# CAN_MicroSDD_IO_Expandor.net
KiCad netlist of a schematic drawn in Altium Designer
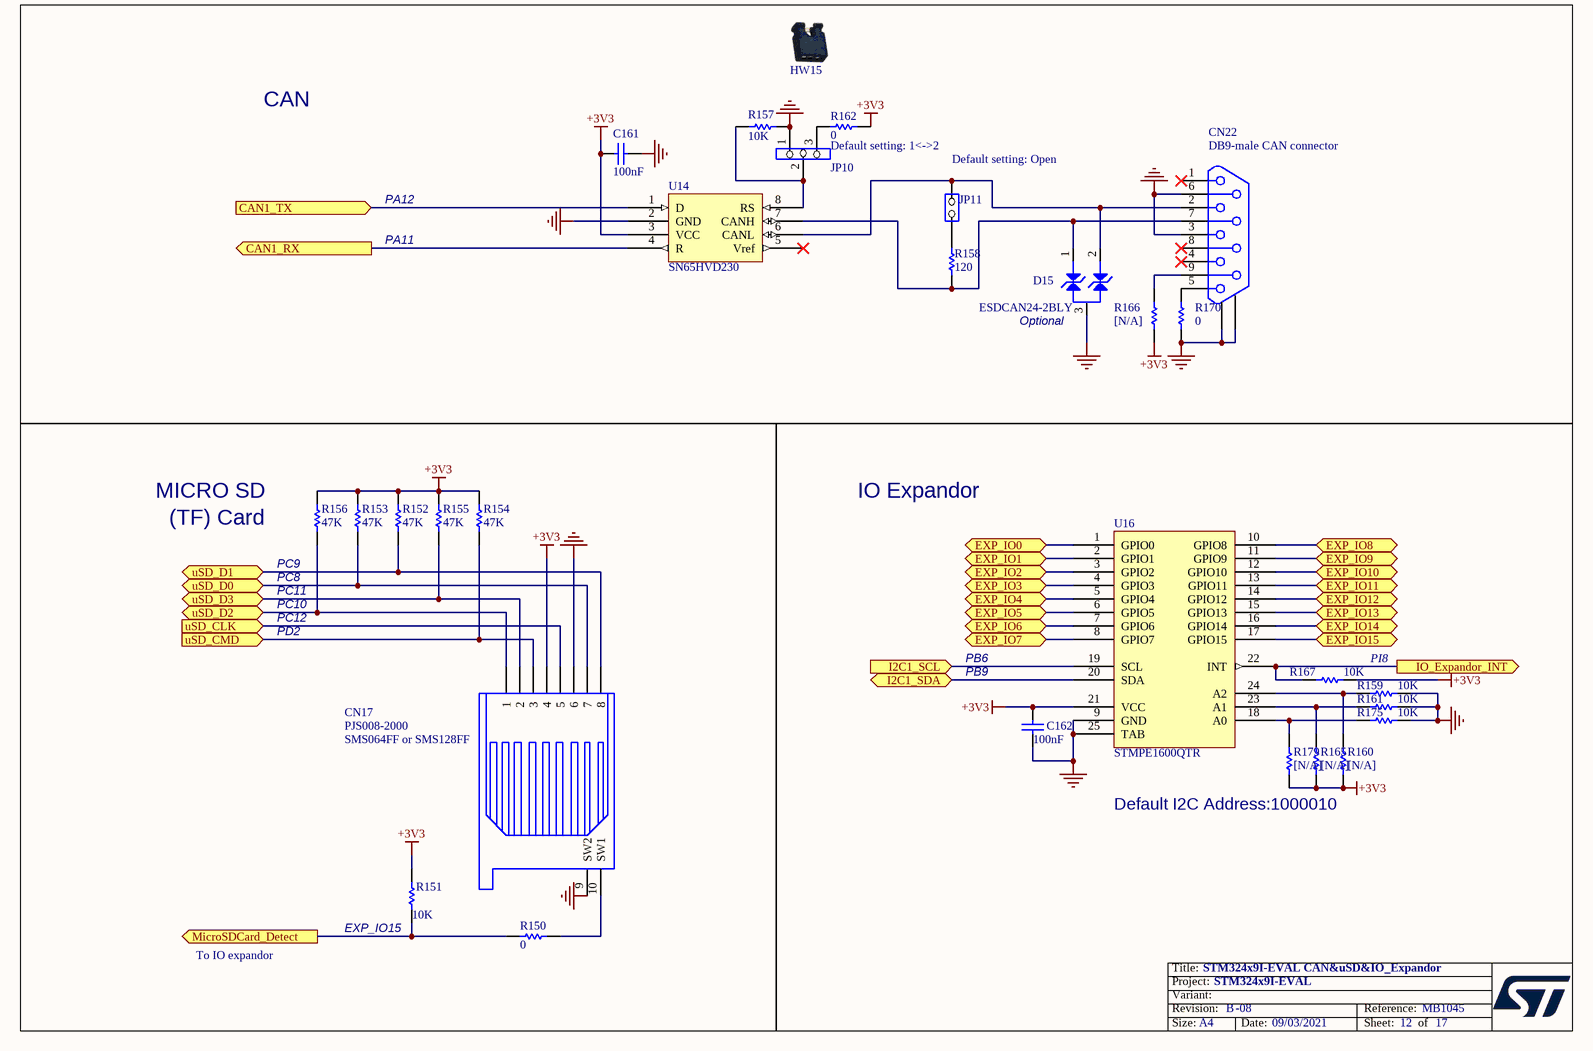
[diagram p0: CAN&MicroSDD&IO_Expandor.SchDoc]

(export (version "E")
  (design (tool "Eeschema 10.0.6"))
  (components
    (comp (ref "C161")
      (value "100nF")
      (footprint "0603C")
      (description "Capacitor")
      (fields (field (name "PUBLISHER") "Altium Limited"))
      (libsource (lib "Miscellaneous Devices") (part "Cap"))
    )
    (comp (ref "C162")
      (value "100nF")
      (footprint "0603C")
      (description "Capacitor")
      (fields (field (name "PUBLISHER") "Altium Limited"))
      (libsource (lib "Miscellaneous Devices") (part "Cap"))
    )
    (comp (ref "CN17")
      (value "PJS008-2000")
      (footprint "MSD_PJS008_")
      (libsource (lib "MB525") (part "SMS016AFA5E"))
    )
    (comp (ref "CN22")
      (value "DB9-male CAN connector")
      (footprint "DB9/M")
      (libsource (lib "mb1045") (part "DB9-CAN"))
    )
    (comp (ref "D15")
      (value "ESDCAN24-2BLY")
      (footprint "SOT23-213")
      (libsource (lib "mb1045") (part "ESDCAN24-2BLY"))
    )
    (comp (ref "HW15") (value "JUMPER_OPEN") (libsource (lib "mb1045") (part "JUMPER_OPEN")))
    (comp (ref "JP10") (value "~") (footprint "SIP3") (libsource (lib "STR910_SCHLIB") (part "Jumper3")))
    (comp (ref "JP11") (value "~") (footprint "SIP2") (libsource (lib "*") (part "JP2")))
    (comp (ref "R150")
      (value "0")
      (footprint "0603R")
      (description "Resistor")
      (fields (field (name "PUBLISHER") "Altium Limited"))
      (libsource (lib "Miscellaneous Devices") (part "Res1"))
    )
    (comp (ref "R151")
      (value "10K")
      (footprint "0603R")
      (description "Resistor")
      (fields (field (name "PUBLISHER") "Altium Limited"))
      (libsource (lib "Miscellaneous Devices") (part "Res1"))
    )
    (comp (ref "R152")
      (value "47K")
      (footprint "0603R")
      (description "Resistor")
      (fields (field (name "PUBLISHER") "Altium Limited"))
      (libsource (lib "Miscellaneous Devices") (part "res1"))
    )
    (comp (ref "R153")
      (value "47K")
      (footprint "0603R")
      (description "Resistor")
      (fields (field (name "PUBLISHER") "Altium Limited"))
      (libsource (lib "Miscellaneous Devices") (part "res1"))
    )
    (comp (ref "R154")
      (value "47K")
      (footprint "0603R")
      (description "Resistor")
      (fields (field (name "PUBLISHER") "Altium Limited"))
      (libsource (lib "Miscellaneous Devices") (part "res1"))
    )
    (comp (ref "R155")
      (value "47K")
      (footprint "0603R")
      (description "Resistor")
      (fields (field (name "PUBLISHER") "Altium Limited"))
      (libsource (lib "Miscellaneous Devices") (part "res1"))
    )
    (comp (ref "R156")
      (value "47K")
      (footprint "0603R")
      (description "Resistor")
      (fields (field (name "PUBLISHER") "Altium Limited"))
      (libsource (lib "Miscellaneous Devices") (part "res1"))
    )
    (comp (ref "R157")
      (value "10K")
      (footprint "0603R")
      (description "Resistor")
      (fields (field (name "PUBLISHER") "Altium Limited"))
      (libsource (lib "Miscellaneous Devices") (part "Res1"))
    )
    (comp (ref "R158")
      (value "120")
      (footprint "0603R")
      (description "Resistor")
      (fields (field (name "PUBLISHER") "Altium Limited"))
      (libsource (lib "Miscellaneous Devices") (part "res1"))
    )
    (comp (ref "R159")
      (value "10K")
      (footprint "0603R")
      (description "Resistor")
      (fields (field (name "PUBLISHER") "Altium Limited"))
      (libsource (lib "Miscellaneous Devices") (part "res1"))
    )
    (comp (ref "R160")
      (value "[N/A]")
      (footprint "0603R")
      (description "Resistor")
      (fields (field (name "PUBLISHER") "Altium Limited"))
      (libsource (lib "Miscellaneous Devices") (part "Res1"))
    )
    (comp (ref "R161")
      (value "10K")
      (footprint "0603R")
      (description "Resistor")
      (fields (field (name "PUBLISHER") "Altium Limited"))
      (libsource (lib "Miscellaneous Devices") (part "res1"))
    )
    (comp (ref "R162")
      (value "0")
      (footprint "0603R")
      (description "Resistor")
      (fields (field (name "PUBLISHER") "Altium Limited"))
      (libsource (lib "Miscellaneous Devices") (part "res1"))
    )
    (comp (ref "R165")
      (value "[N/A]")
      (footprint "0603R")
      (description "Resistor")
      (fields (field (name "PUBLISHER") "Altium Limited"))
      (libsource (lib "Miscellaneous Devices") (part "Res1"))
    )
    (comp (ref "R166")
      (value "[N/A]")
      (footprint "0603R")
      (description "Resistor")
      (fields (field (name "PUBLISHER") "Altium Limited"))
      (libsource (lib "Miscellaneous Devices") (part "res1"))
    )
    (comp (ref "R167")
      (value "10K")
      (footprint "0603R")
      (description "Resistor")
      (fields (field (name "PUBLISHER") "Altium Limited"))
      (libsource (lib "Miscellaneous Devices") (part "Res1"))
    )
    (comp (ref "R170")
      (value "0")
      (footprint "0603R")
      (description "Resistor")
      (fields (field (name "PUBLISHER") "Altium Limited"))
      (libsource (lib "Miscellaneous Devices") (part "res1"))
    )
    (comp (ref "R175")
      (value "10K")
      (footprint "0603R")
      (description "Resistor")
      (fields (field (name "PUBLISHER") "Altium Limited"))
      (libsource (lib "Miscellaneous Devices") (part "res1"))
    )
    (comp (ref "R179")
      (value "[N/A]")
      (footprint "0603R")
      (description "Resistor")
      (fields (field (name "PUBLISHER") "Altium Limited"))
      (libsource (lib "Miscellaneous Devices") (part "Res1"))
    )
    (comp (ref "U14")
      (value "SN65HVD230")
      (footprint "SOIC8_1R27_4R9X6")
      (libsource (lib "STR910_SCHLIB") (part "SN65HVD230D"))
    )
    (comp (ref "U16")
      (value "STMPE1600QTR")
      (footprint "QFN24_0R5_4X4")
      (libsource (lib "mb1045") (part "STMPE1600"))
    )
  )
  (nets
    (net (code "1") (name "+3V3") (class "Default")
      (node (ref "C161") (pin "1") (pinfunction "1_1") (pintype "passive"))
      (node (ref "C162") (pin "1") (pinfunction "1_1") (pintype "passive"))
      (node (ref "CN17") (pin "4") (pinfunction "4_4") (pintype "passive"))
      (node (ref "R151") (pin "2") (pinfunction "2_2") (pintype "passive"))
      (node (ref "R152") (pin "1") (pinfunction "1_1") (pintype "passive"))
      (node (ref "R153") (pin "1") (pinfunction "1_1") (pintype "passive"))
      (node (ref "R154") (pin "1") (pinfunction "1_1") (pintype "passive"))
      (node (ref "R155") (pin "1") (pinfunction "1_1") (pintype "passive"))
      (node (ref "R156") (pin "1") (pinfunction "1_1") (pintype "passive"))
      (node (ref "R160") (pin "1") (pinfunction "1_1") (pintype "passive"))
      (node (ref "R162") (pin "2") (pinfunction "2_2") (pintype "passive"))
      (node (ref "R165") (pin "1") (pinfunction "1_1") (pintype "passive"))
      (node (ref "R166") (pin "1") (pinfunction "1_1") (pintype "passive"))
      (node (ref "R167") (pin "1") (pinfunction "1_1") (pintype "passive"))
      (node (ref "R179") (pin "1") (pinfunction "1_1") (pintype "passive"))
      (node (ref "U14") (pin "3") (pinfunction "VCC_3") (pintype "power_in"))
      (node (ref "U16") (pin "21") (pinfunction "VCC_21") (pintype "passive"))
    )
    (net (code "2") (name "/CAN1_RX") (class "Default")
      (node (ref "U14") (pin "4") (pinfunction "R_4") (pintype "output"))
    )
    (net (code "3") (name "/CAN1_TX") (class "Default")
      (node (ref "U14") (pin "1") (pinfunction "D_1") (pintype "input"))
    )
    (net (code "4") (name "/EXP_IO0") (class "Default")
      (node (ref "U16") (pin "1") (pinfunction "GPIO0_1") (pintype "passive"))
    )
    (net (code "5") (name "/EXP_IO1") (class "Default")
      (node (ref "U16") (pin "2") (pinfunction "GPIO1_2") (pintype "passive"))
    )
    (net (code "6") (name "/EXP_IO2") (class "Default")
      (node (ref "U16") (pin "3") (pinfunction "GPIO2_3") (pintype "passive"))
    )
    (net (code "7") (name "/EXP_IO3") (class "Default")
      (node (ref "U16") (pin "4") (pinfunction "GPIO3_4") (pintype "passive"))
    )
    (net (code "8") (name "/EXP_IO4") (class "Default")
      (node (ref "U16") (pin "5") (pinfunction "GPIO4_5") (pintype "passive"))
    )
    (net (code "9") (name "/EXP_IO5") (class "Default")
      (node (ref "U16") (pin "6") (pinfunction "GPIO5_6") (pintype "passive"))
    )
    (net (code "10") (name "/EXP_IO6") (class "Default")
      (node (ref "U16") (pin "7") (pinfunction "GPIO6_7") (pintype "passive"))
    )
    (net (code "11") (name "/EXP_IO7") (class "Default")
      (node (ref "U16") (pin "8") (pinfunction "GPIO7_8") (pintype "passive"))
    )
    (net (code "12") (name "/EXP_IO8") (class "Default")
      (node (ref "U16") (pin "10") (pinfunction "GPIO8_10") (pintype "passive"))
    )
    (net (code "13") (name "/EXP_IO9") (class "Default")
      (node (ref "U16") (pin "11") (pinfunction "GPIO9_11") (pintype "passive"))
    )
    (net (code "14") (name "/EXP_IO10") (class "Default")
      (node (ref "U16") (pin "12") (pinfunction "GPIO10_12") (pintype "passive"))
    )
    (net (code "15") (name "/EXP_IO11") (class "Default")
      (node (ref "U16") (pin "13") (pinfunction "GPIO11_13") (pintype "passive"))
    )
    (net (code "16") (name "/EXP_IO12") (class "Default")
      (node (ref "U16") (pin "14") (pinfunction "GPIO12_14") (pintype "passive"))
    )
    (net (code "17") (name "/EXP_IO13") (class "Default")
      (node (ref "U16") (pin "15") (pinfunction "GPIO13_15") (pintype "passive"))
    )
    (net (code "18") (name "/EXP_IO14") (class "Default")
      (node (ref "U16") (pin "16") (pinfunction "GPIO14_16") (pintype "passive"))
    )
    (net (code "19") (name "/EXP_IO15") (class "Default")
      (node (ref "U16") (pin "17") (pinfunction "GPIO15_17") (pintype "passive"))
    )
    (net (code "20") (name "/I2C1_SCL") (class "Default")
      (node (ref "U16") (pin "19") (pinfunction "SCL_19") (pintype "passive"))
    )
    (net (code "21") (name "/I2C1_SDA") (class "Default")
      (node (ref "U16") (pin "20") (pinfunction "SDA_20") (pintype "passive"))
    )
    (net (code "22") (name "/IO_Expandor_INT") (class "Default")
      (node (ref "R167") (pin "2") (pinfunction "2_2") (pintype "passive"))
      (node (ref "U16") (pin "22") (pinfunction "INT_22") (pintype "output"))
    )
    (net (code "23") (name "/MicroSDCard_Detect") (class "Default")
      (node (ref "R150") (pin "1") (pinfunction "1_1") (pintype "passive"))
      (node (ref "R151") (pin "1") (pinfunction "1_1") (pintype "passive"))
    )
    (net (code "24") (name "/uSD_CLK") (class "Default")
      (node (ref "CN17") (pin "5") (pinfunction "5_5") (pintype "passive"))
    )
    (net (code "25") (name "/uSD_CMD") (class "Default")
      (node (ref "CN17") (pin "3") (pinfunction "3_3") (pintype "passive"))
      (node (ref "R154") (pin "2") (pinfunction "2_2") (pintype "passive"))
    )
    (net (code "26") (name "/uSD_D0") (class "Default")
      (node (ref "CN17") (pin "7") (pinfunction "7_7") (pintype "passive"))
      (node (ref "R153") (pin "2") (pinfunction "2_2") (pintype "passive"))
    )
    (net (code "27") (name "/uSD_D1") (class "Default")
      (node (ref "CN17") (pin "8") (pinfunction "8_8") (pintype "passive"))
      (node (ref "R152") (pin "2") (pinfunction "2_2") (pintype "passive"))
    )
    (net (code "28") (name "/uSD_D2") (class "Default")
      (node (ref "CN17") (pin "1") (pinfunction "1_1") (pintype "passive"))
      (node (ref "R156") (pin "2") (pinfunction "2_2") (pintype "passive"))
    )
    (net (code "29") (name "/uSD_D3") (class "Default")
      (node (ref "CN17") (pin "2") (pinfunction "2_2") (pintype "passive"))
      (node (ref "R155") (pin "2") (pinfunction "2_2") (pintype "passive"))
    )
    (net (code "30") (name "GND") (class "Default")
      (node (ref "C161") (pin "2") (pinfunction "2_2") (pintype "passive"))
      (node (ref "C162") (pin "2") (pinfunction "2_2") (pintype "passive"))
      (node (ref "CN17") (pin "6") (pinfunction "6_6") (pintype "passive"))
      (node (ref "CN17") (pin "9") (pinfunction "SW2_9") (pintype "passive"))
      (node (ref "CN22") (pin "10") (pinfunction "10_10") (pintype "passive"))
      (node (ref "CN22") (pin "11") (pinfunction "11_11") (pintype "passive"))
      (node (ref "CN22") (pin "3") (pinfunction "3_3") (pintype "passive"))
      (node (ref "CN22") (pin "6") (pinfunction "6_6") (pintype "passive"))
      (node (ref "D15") (pin "3") (pinfunction "3_3") (pintype "passive"))
      (node (ref "JP10") (pin "1") (pintype "passive"))
      (node (ref "R157") (pin "2") (pinfunction "2_2") (pintype "passive"))
      (node (ref "R159") (pin "1") (pinfunction "1_1") (pintype "passive"))
      (node (ref "R161") (pin "1") (pinfunction "1_1") (pintype "passive"))
      (node (ref "R170") (pin "1") (pinfunction "1_1") (pintype "passive"))
      (node (ref "R175") (pin "1") (pinfunction "1_1") (pintype "passive"))
      (node (ref "U14") (pin "2") (pinfunction "GND_2") (pintype "power_in"))
      (node (ref "U16") (pin "25") (pinfunction "TAB_25") (pintype "passive"))
      (node (ref "U16") (pin "9") (pinfunction "GND_9") (pintype "passive"))
    )
    (net (code "31") (name "Net-(CN17-SW1)") (class "Default")
      (node (ref "CN17") (pin "10") (pinfunction "SW1_10") (pintype "passive"))
      (node (ref "R150") (pin "2") (pinfunction "2_2") (pintype "passive"))
    )
    (net (code "32") (name "Net-(CN22-Pad5)") (class "Default")
      (node (ref "CN22") (pin "5") (pinfunction "5_5") (pintype "passive"))
      (node (ref "R170") (pin "2") (pinfunction "2_2") (pintype "passive"))
    )
    (net (code "33") (name "Net-(CN22-Pad9)") (class "Default")
      (node (ref "CN22") (pin "9") (pinfunction "9_9") (pintype "passive"))
      (node (ref "R166") (pin "2") (pinfunction "2_2") (pintype "passive"))
    )
    (net (code "34") (name "Net-(JP10-Pad3)") (class "Default")
      (node (ref "JP10") (pin "3") (pintype "passive"))
      (node (ref "R162") (pin "1") (pinfunction "1_1") (pintype "passive"))
    )
    (net (code "35") (name "Net-(JP11-COMMON)") (class "Default")
      (node (ref "JP11") (pin "1") (pinfunction "COMMON_1") (pintype "passive"))
      (node (ref "R158") (pin "2") (pinfunction "2_2") (pintype "passive"))
    )
    (net (code "36") (name "Net-(JP11-NO)") (class "Default")
      (node (ref "CN22") (pin "2") (pinfunction "2_2") (pintype "passive"))
      (node (ref "D15") (pin "2") (pinfunction "2_2") (pintype "passive"))
      (node (ref "JP11") (pin "2") (pinfunction "NO_2") (pintype "passive"))
      (node (ref "U14") (pin "6") (pinfunction "CANL_6") (pintype "bidirectional"))
    )
    (net (code "37") (name "Net-(U14-CANH)") (class "Default")
      (node (ref "CN22") (pin "7") (pinfunction "7_7") (pintype "passive"))
      (node (ref "D15") (pin "1") (pinfunction "1_1") (pintype "passive"))
      (node (ref "R158") (pin "1") (pinfunction "1_1") (pintype "passive"))
      (node (ref "U14") (pin "7") (pinfunction "CANH_7") (pintype "bidirectional"))
    )
    (net (code "38") (name "Net-(U14-RS)") (class "Default")
      (node (ref "JP10") (pin "2") (pintype "passive"))
      (node (ref "R157") (pin "1") (pinfunction "1_1") (pintype "passive"))
      (node (ref "U14") (pin "8") (pinfunction "RS_8") (pintype "input"))
    )
    (net (code "39") (name "Net-(U16-A0)") (class "Default")
      (node (ref "R175") (pin "2") (pinfunction "2_2") (pintype "passive"))
      (node (ref "R179") (pin "2") (pinfunction "2_2") (pintype "passive"))
      (node (ref "U16") (pin "18") (pinfunction "A0_18") (pintype "passive"))
    )
    (net (code "40") (name "Net-(U16-A1)") (class "Default")
      (node (ref "R161") (pin "2") (pinfunction "2_2") (pintype "passive"))
      (node (ref "R165") (pin "2") (pinfunction "2_2") (pintype "passive"))
      (node (ref "U16") (pin "23") (pinfunction "A1_23") (pintype "passive"))
    )
    (net (code "41") (name "Net-(U16-A2)") (class "Default")
      (node (ref "R159") (pin "2") (pinfunction "2_2") (pintype "passive"))
      (node (ref "R160") (pin "2") (pinfunction "2_2") (pintype "passive"))
      (node (ref "U16") (pin "24") (pinfunction "A2_24") (pintype "passive"))
    )
    (net (code "42") (name "unconnected-(CN22-Pad1)") (class "Default")
      (node (ref "CN22") (pin "1") (pinfunction "1_1") (pintype "passive+no_connect"))
    )
    (net (code "43") (name "unconnected-(CN22-Pad4)") (class "Default")
      (node (ref "CN22") (pin "4") (pinfunction "4_4") (pintype "passive+no_connect"))
    )
    (net (code "44") (name "unconnected-(CN22-Pad8)") (class "Default")
      (node (ref "CN22") (pin "8") (pinfunction "8_8") (pintype "passive+no_connect"))
    )
    (net (code "45") (name "unconnected-(U14-Vref-Pad5)") (class "Default")
      (node (ref "U14") (pin "5") (pinfunction "Vref_5") (pintype "output+no_connect"))
    )
  )
)
